# SENSOR_SCH_FPC.net
KiCad netlist of a schematic drawn in EasyEDA
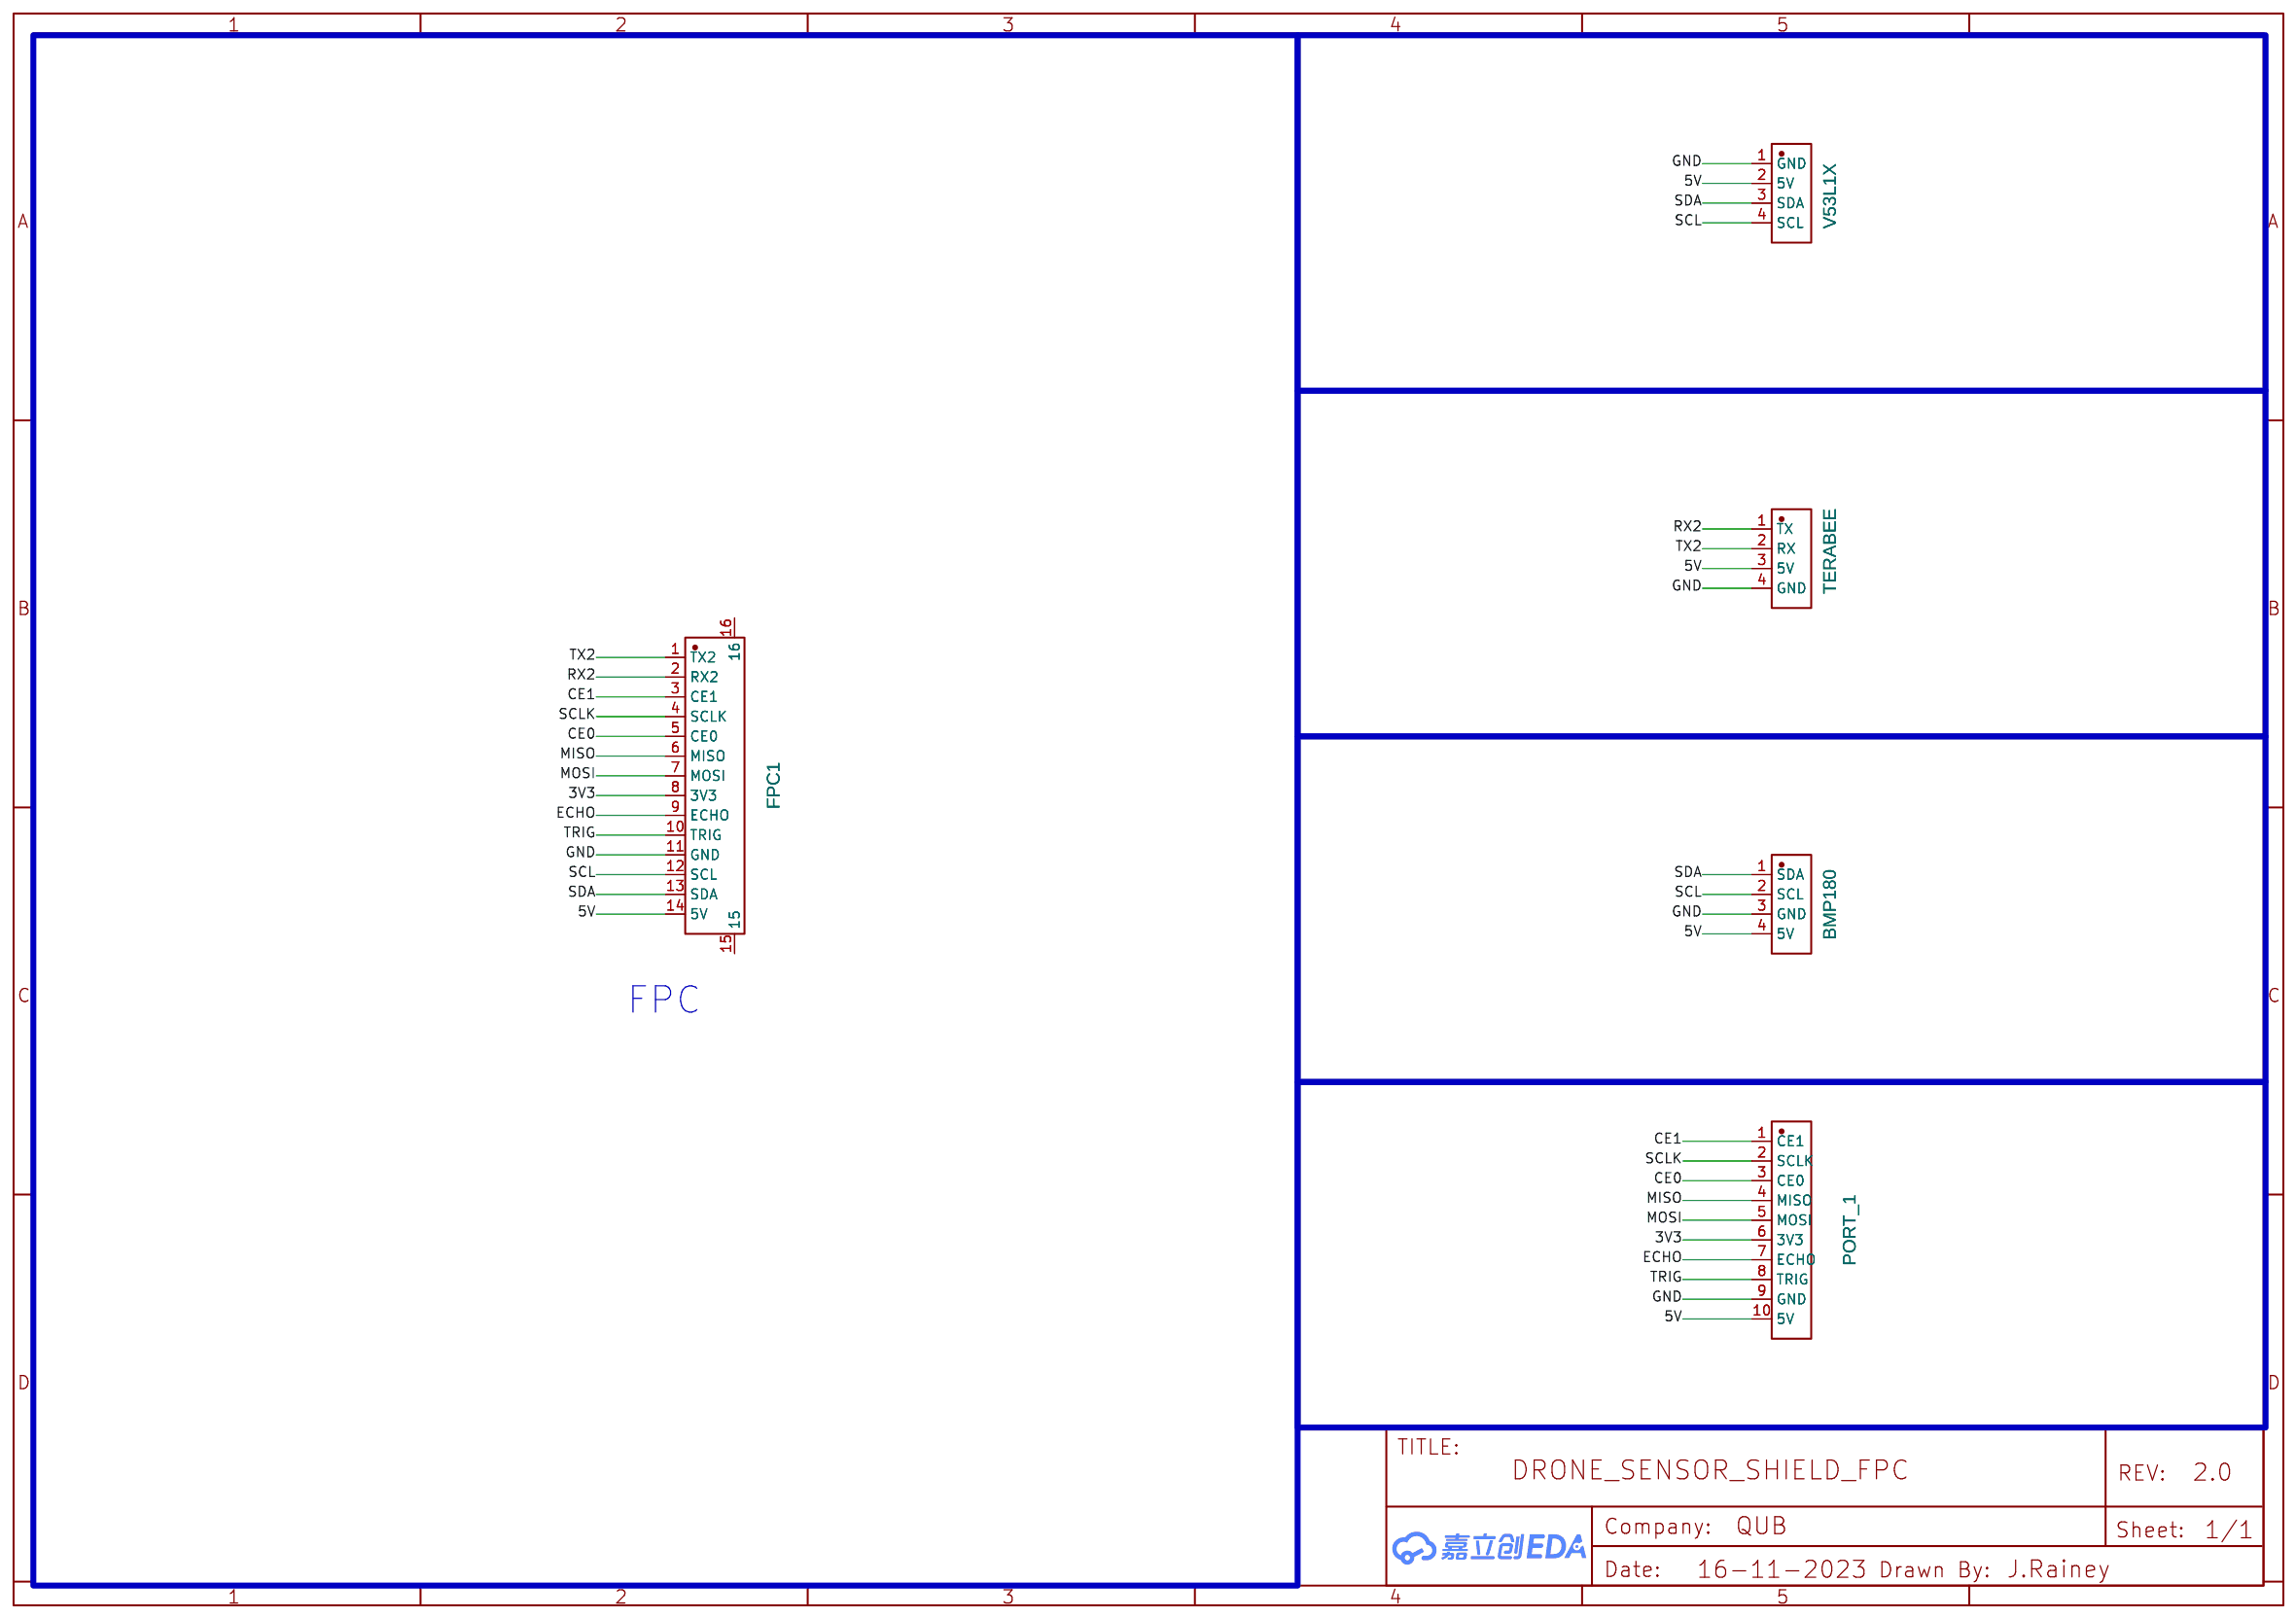
[diagram p0: schematic sheet]

(export (version "E")
  (design (tool "Eeschema 10.0.6"))
  (components
    (comp (ref "BMP180")
      (value "PZ254V-11-04P")
      (fields (field (name "BOM_Supplier Part") "C492403"))
      (libsource (lib "") (part "PZ254V-11-04P"))
    )
    (comp (ref "FPC1")
      (value "1.0K-FX-14PWB")
      (fields (field (name "Manufacturer") "HDGC(华德共创)"))
      (libsource (lib "") (part "1.0K-FX-14PWB"))
    )
    (comp (ref "PORT_1")
      (value "PORT_1")
      (fields (field (name "Manufacturer Part") "cn10_2r54_10x1"))
      (libsource (lib "") (part "CN10_2R54_10X1"))
    )
    (comp (ref "TERABEE")
      (value "PZ254V-11-04P")
      (fields (field (name "BOM_Supplier Part") "C492403"))
      (libsource (lib "") (part "PZ254V-11-04P_1"))
    )
    (comp (ref "V53L1X")
      (value "PZ254V-11-04P")
      (fields (field (name "BOM_Supplier Part") "C492403"))
      (libsource (lib "") (part "PZ254V-11-04P_2"))
    )
  )
  (nets
    (net (code "1") (name "/3V3") (class "Default")
      (node (ref "FPC1") (pin "8") (pinfunction "3V3_8") (pintype "unspecified"))
      (node (ref "PORT_1") (pin "6") (pinfunction "3V3_6") (pintype "unspecified"))
    )
    (net (code "2") (name "/5V") (class "Default")
      (node (ref "BMP180") (pin "4") (pinfunction "5V_4") (pintype "unspecified"))
      (node (ref "FPC1") (pin "14") (pinfunction "5V_14") (pintype "unspecified"))
      (node (ref "PORT_1") (pin "10") (pinfunction "5V_10") (pintype "unspecified"))
      (node (ref "TERABEE") (pin "3") (pinfunction "5V_3") (pintype "unspecified"))
      (node (ref "V53L1X") (pin "2") (pinfunction "5V_2") (pintype "unspecified"))
    )
    (net (code "3") (name "/CE0") (class "Default")
      (node (ref "FPC1") (pin "5") (pinfunction "CE0_5") (pintype "unspecified"))
      (node (ref "PORT_1") (pin "3") (pinfunction "CE0_3") (pintype "unspecified"))
    )
    (net (code "4") (name "/CE1") (class "Default")
      (node (ref "FPC1") (pin "3") (pinfunction "CE1_3") (pintype "unspecified"))
      (node (ref "PORT_1") (pin "1") (pinfunction "CE1_1") (pintype "unspecified"))
    )
    (net (code "5") (name "/ECHO") (class "Default")
      (node (ref "FPC1") (pin "9") (pinfunction "ECHO_9") (pintype "unspecified"))
      (node (ref "PORT_1") (pin "7") (pinfunction "ECHO_7") (pintype "unspecified"))
    )
    (net (code "6") (name "/GND") (class "Default")
      (node (ref "BMP180") (pin "3") (pinfunction "GND_3") (pintype "unspecified"))
      (node (ref "FPC1") (pin "11") (pinfunction "GND_11") (pintype "unspecified"))
      (node (ref "PORT_1") (pin "9") (pinfunction "GND_9") (pintype "unspecified"))
      (node (ref "TERABEE") (pin "4") (pinfunction "GND_4") (pintype "unspecified"))
      (node (ref "V53L1X") (pin "1") (pinfunction "GND_1") (pintype "unspecified"))
    )
    (net (code "7") (name "/MISO") (class "Default")
      (node (ref "FPC1") (pin "6") (pinfunction "MISO_6") (pintype "unspecified"))
      (node (ref "PORT_1") (pin "4") (pinfunction "MISO_4") (pintype "unspecified"))
    )
    (net (code "8") (name "/MOSI") (class "Default")
      (node (ref "FPC1") (pin "7") (pinfunction "MOSI_7") (pintype "unspecified"))
      (node (ref "PORT_1") (pin "5") (pinfunction "MOSI_5") (pintype "unspecified"))
    )
    (net (code "9") (name "/RX2") (class "Default")
      (node (ref "FPC1") (pin "2") (pinfunction "RX2_2") (pintype "unspecified"))
      (node (ref "TERABEE") (pin "1") (pinfunction "TX_1") (pintype "unspecified"))
    )
    (net (code "10") (name "/SCL") (class "Default")
      (node (ref "BMP180") (pin "2") (pinfunction "SCL_2") (pintype "unspecified"))
      (node (ref "FPC1") (pin "12") (pinfunction "SCL_12") (pintype "unspecified"))
      (node (ref "V53L1X") (pin "4") (pinfunction "SCL_4") (pintype "unspecified"))
    )
    (net (code "11") (name "/SCLK") (class "Default")
      (node (ref "FPC1") (pin "4") (pinfunction "SCLK_4") (pintype "unspecified"))
      (node (ref "PORT_1") (pin "2") (pinfunction "SCLK_2") (pintype "unspecified"))
    )
    (net (code "12") (name "/SDA") (class "Default")
      (node (ref "BMP180") (pin "1") (pinfunction "SDA_1") (pintype "unspecified"))
      (node (ref "FPC1") (pin "13") (pinfunction "SDA_13") (pintype "unspecified"))
      (node (ref "V53L1X") (pin "3") (pinfunction "SDA_3") (pintype "unspecified"))
    )
    (net (code "13") (name "/TRIG") (class "Default")
      (node (ref "FPC1") (pin "10") (pinfunction "TRIG_10") (pintype "unspecified"))
      (node (ref "PORT_1") (pin "8") (pinfunction "TRIG_8") (pintype "unspecified"))
    )
    (net (code "14") (name "/TX2") (class "Default")
      (node (ref "FPC1") (pin "1") (pinfunction "TX2_1") (pintype "unspecified"))
      (node (ref "TERABEE") (pin "2") (pinfunction "RX_2") (pintype "unspecified"))
    )
    (net (code "15") (name "unconnected-(FPC1-Pad15)") (class "Default")
      (node (ref "FPC1") (pin "15") (pinfunction "15_15") (pintype "unspecified"))
    )
    (net (code "16") (name "unconnected-(FPC1-Pad16)") (class "Default")
      (node (ref "FPC1") (pin "16") (pinfunction "16_16") (pintype "unspecified"))
    )
  )
)
